# RELAY14.net
KiCad netlist of a schematic drawn in Altium Designer
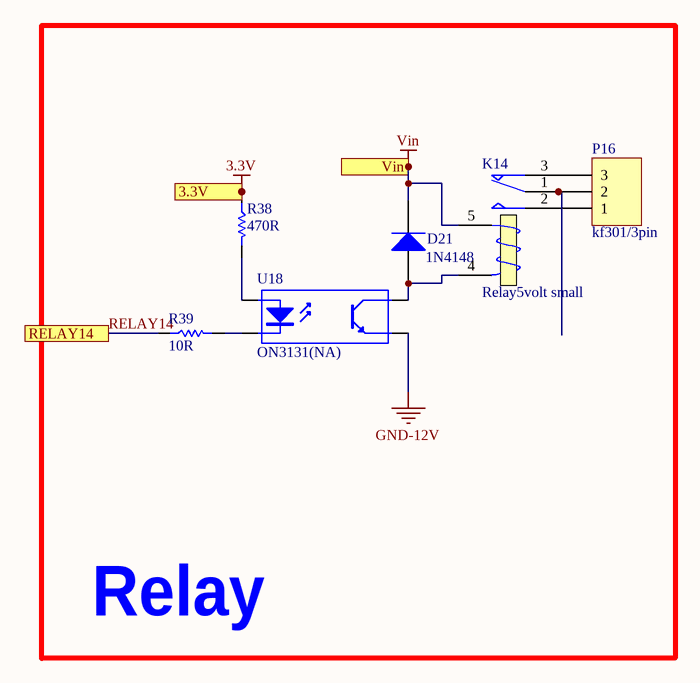
[diagram p0: RELAY14.SchDoc]

(export (version "E")
  (design (tool "Eeschema 10.0.6"))
  (components
    (comp (ref "D21")
      (value "1N4148")
      (footprint "sod123")
      (description "1 Amp General Purpose Rectifier")
      (fields (field (name "PUBLISHER") "Altium Limited"))
      (libsource (lib "Miscellaneous Devices") (part "Diode 1N4007"))
    )
    (comp (ref "K14")
      (value "Relay5volt small")
      (footprint "relay5_childern")
      (description "SPDT Relay")
      (fields (field (name "PUBLISHER") "Altium Limited"))
      (libsource (lib "FLIB") (part "Relay"))
    )
    (comp (ref "P16")
      (value "kf301/3pin")
      (footprint "Blue Connector 1*3 -kf301")
      (fields (field (name "PUBLISHER") "Altium Limited"))
      (libsource (lib "Miscellaneous Connectors") (part "Header 3"))
    )
    (comp (ref "R38")
      (value "470R")
      (footprint "0805/resistor")
      (description "Resistor")
      (fields (field (name "TOLERANCE") "5%") (field (name "POWER") "1/8 W"))
      (libsource (lib "skille") (part "Resistor"))
    )
    (comp (ref "R39")
      (value "10R")
      (footprint "0805/resistor")
      (description "Resistor")
      (fields (field (name "TOLERANCE") "5%") (field (name "POWER") "1/8 W"))
      (libsource (lib "skille") (part "Resistor"))
    )
    (comp (ref "U18")
      (value "ON3131(NA)")
      (footprint "OPTO_COUPLER")
      (description "4-Pin Phototransistor Optocoupler")
      (fields (field (name "PUBLISHER") "Altium Limited"))
      (libsource (lib "skille") (part "Optoisolator1"))
    )
  )
  (nets
    (net (code "1") (name "/RELAY14") (class "Default")
      (node (ref "R39") (pin "1") (pinfunction "1_1") (pintype "passive"))
    )
    (net (code "2") (name "3.3V") (class "Default")
      (node (ref "R38") (pin "1") (pinfunction "1_1") (pintype "passive"))
    )
    (net (code "3") (name "GND-12V") (class "Default")
      (node (ref "U18") (pin "3") (pinfunction "E_3") (pintype "passive"))
    )
    (net (code "4") (name "Net-(K14-COM)") (class "Default")
      (node (ref "K14") (pin "1") (pinfunction "COM_1") (pintype "passive"))
      (node (ref "P16") (pin "2") (pinfunction "2_2") (pintype "passive"))
    )
    (net (code "5") (name "Net-(K14-NO)") (class "Default")
      (node (ref "K14") (pin "2") (pinfunction "NO_2") (pintype "passive"))
      (node (ref "P16") (pin "1") (pinfunction "1_1") (pintype "passive"))
    )
    (net (code "6") (name "Net-(K14-T1)") (class "Default")
      (node (ref "K14") (pin "3") (pinfunction "T1_3") (pintype "passive"))
      (node (ref "P16") (pin "3") (pinfunction "3_3") (pintype "passive"))
    )
    (net (code "7") (name "Net-(K14-T2)") (class "Default")
      (node (ref "D21") (pin "A") (pinfunction "A_A") (pintype "passive"))
      (node (ref "K14") (pin "4") (pinfunction "T2_4") (pintype "passive"))
      (node (ref "U18") (pin "4") (pinfunction "C_4") (pintype "passive"))
    )
    (net (code "8") (name "Net-(U18-A)") (class "Default")
      (node (ref "R38") (pin "2") (pinfunction "2_2") (pintype "passive"))
      (node (ref "U18") (pin "1") (pinfunction "A_1") (pintype "passive"))
    )
    (net (code "9") (name "Net-(U18-K)") (class "Default")
      (node (ref "R39") (pin "2") (pinfunction "2_2") (pintype "passive"))
      (node (ref "U18") (pin "2") (pinfunction "K_2") (pintype "passive"))
    )
    (net (code "10") (name "Vin") (class "Default")
      (node (ref "D21") (pin "K") (pinfunction "K_K") (pintype "passive"))
      (node (ref "K14") (pin "5") (pinfunction "5_5") (pintype "passive"))
    )
  )
)
